# 5Wled-mosfet.net
KiCad netlist of a schematic drawn in EAGLE
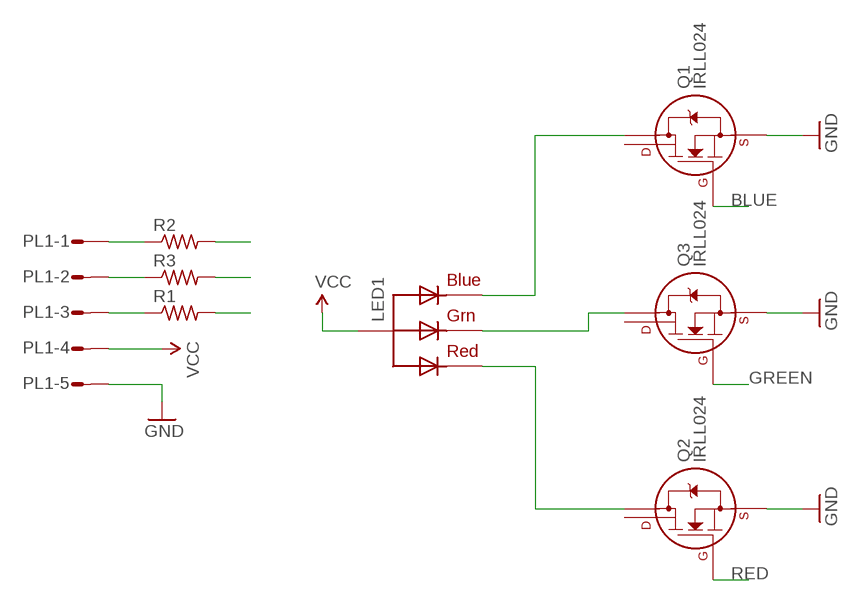
[diagram p0: schematic, sheet 1]

(export (version "E")
  (design (tool "Eeschema 10.0.6"))
  (components
    (comp (ref "LED1")
      (value "RGBLED_CA4.5MM")
      (footprint "eagle-import:5WRGBLED")
      (libsource (lib "eagle-import") (part "RGBLED_CA4.5MM"))
    )
    (comp (ref "PL1")
      (value "DF3-05R")
      (footprint "eagle-import:DF3R-05")
      (libsource (lib "eagle-import") (part "DF3-05R"))
    )
    (comp (ref "Q1")
      (value "IRLL024")
      (footprint "eagle-import:SOT-223")
      (libsource (lib "eagle-import") (part "IRLL024"))
    )
    (comp (ref "Q2")
      (value "IRLL024")
      (footprint "eagle-import:SOT-223")
      (libsource (lib "eagle-import") (part "IRLL024"))
    )
    (comp (ref "Q3")
      (value "IRLL024")
      (footprint "eagle-import:SOT-223")
      (libsource (lib "eagle-import") (part "IRLL024"))
    )
    (comp (ref "R1")
      (value "R-US_0204/5")
      (footprint "eagle-import:0204_5")
      (libsource (lib "eagle-import") (part "R-US_0204/5"))
    )
    (comp (ref "R2")
      (value "R-US_0204/5")
      (footprint "eagle-import:0204_5")
      (libsource (lib "eagle-import") (part "R-US_0204/5"))
    )
    (comp (ref "R3")
      (value "R-US_0204/5")
      (footprint "eagle-import:0204_5")
      (libsource (lib "eagle-import") (part "R-US_0204/5"))
    )
  )
  (nets
    (net (code "1") (name "/BLUE") (class "Default")
      (node (ref "Q1") (pin "1") (pinfunction "G_1") (pintype "tri_state"))
      (node (ref "R1") (pin "2") (pinfunction "2_2") (pintype "passive"))
    )
    (net (code "2") (name "/GREEN") (class "Default")
      (node (ref "Q3") (pin "1") (pinfunction "G_1") (pintype "tri_state"))
      (node (ref "R3") (pin "2") (pinfunction "2_2") (pintype "passive"))
    )
    (net (code "3") (name "/RED") (class "Default")
      (node (ref "Q2") (pin "1") (pinfunction "G_1") (pintype "tri_state"))
      (node (ref "R2") (pin "2") (pinfunction "2_2") (pintype "passive"))
    )
    (net (code "4") (name "GND") (class "Default")
      (node (ref "PL1") (pin "5") (pinfunction "S_5") (pintype "passive"))
      (node (ref "Q1") (pin "3") (pinfunction "S_3") (pintype "bidirectional"))
      (node (ref "Q2") (pin "3") (pinfunction "S_3") (pintype "bidirectional"))
      (node (ref "Q3") (pin "3") (pinfunction "S_3") (pintype "bidirectional"))
    )
    (net (code "5") (name "Net-(LED1-BLUE)") (class "Default")
      (node (ref "LED1") (pin "1") (pinfunction "BLUE_1") (pintype "bidirectional"))
      (node (ref "Q1") (pin "2") (pinfunction "D1_2") (pintype "bidirectional"))
    )
    (net (code "6") (name "Net-(LED1-GREEN)") (class "Default")
      (node (ref "LED1") (pin "3") (pinfunction "GREEN_3") (pintype "bidirectional"))
      (node (ref "Q3") (pin "2") (pinfunction "D1_2") (pintype "bidirectional"))
    )
    (net (code "7") (name "Net-(LED1-RED)") (class "Default")
      (node (ref "LED1") (pin "2") (pinfunction "RED_2") (pintype "bidirectional"))
      (node (ref "Q2") (pin "2") (pinfunction "D1_2") (pintype "bidirectional"))
    )
    (net (code "8") (name "Net-(PL1A-S)") (class "Default")
      (node (ref "PL1") (pin "1") (pinfunction "S_1") (pintype "passive"))
      (node (ref "R2") (pin "1") (pinfunction "1_1") (pintype "passive"))
    )
    (net (code "9") (name "Net-(PL1B-S)") (class "Default")
      (node (ref "PL1") (pin "2") (pinfunction "S_2") (pintype "passive"))
      (node (ref "R3") (pin "1") (pinfunction "1_1") (pintype "passive"))
    )
    (net (code "10") (name "Net-(PL1C-S)") (class "Default")
      (node (ref "PL1") (pin "3") (pinfunction "S_3") (pintype "passive"))
      (node (ref "R1") (pin "1") (pinfunction "1_1") (pintype "passive"))
    )
    (net (code "11") (name "VCC") (class "Default")
      (node (ref "LED1") (pin "4") (pinfunction "VCC_4") (pintype "bidirectional"))
      (node (ref "PL1") (pin "4") (pinfunction "S_4") (pintype "passive"))
    )
    (net (code "12") (name "unconnected-(Q1-D2-Pad4)") (class "Default")
      (node (ref "Q1") (pin "4") (pinfunction "D2_4") (pintype "bidirectional"))
    )
    (net (code "13") (name "unconnected-(Q2-D2-Pad4)") (class "Default")
      (node (ref "Q2") (pin "4") (pinfunction "D2_4") (pintype "bidirectional"))
    )
    (net (code "14") (name "unconnected-(Q3-D2-Pad4)") (class "Default")
      (node (ref "Q3") (pin "4") (pinfunction "D2_4") (pintype "bidirectional"))
    )
  )
)
